# Heat_Controller.net
KiCad netlist of a schematic drawn in Altium Designer
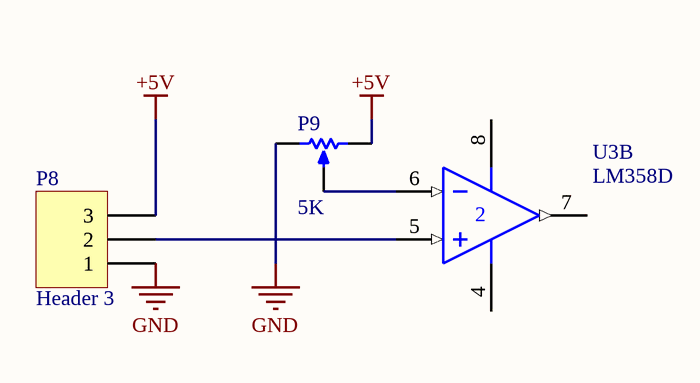
[diagram p0: Heat Controller.SchDoc]

(export (version "E")
  (design (tool "Eeschema 10.0.6"))
  (components
    (comp (ref "P8")
      (value "Header 3")
      (footprint "HDR1X3")
      (description "Header, 3-Pin")
      (fields (field (name "PUBLISHER") "Altium Limited"))
      (libsource (lib "Miscellaneous Connectors") (part "Header 3"))
    )
    (comp (ref "P9")
      (value "5K")
      (footprint "TRIMPOT-3296W")
      (libsource (lib "CustomLibrary") (part "TRIMPOT"))
    )
    (comp (ref "U3")
      (value "LM358D")
      (footprint "751-02_N")
      (description "Dual Low-Power Operational Amplifier")
      (fields (field (name "PUBLISHER") "Altium Limited"))
      (libsource (lib "Motorola Amplifier Operational Amplifier") (part "LM358D"))
    )
  )
  (nets
    (net (code "1") (name "+5V") (class "Default")
      (node (ref "P8") (pin "3") (pinfunction "3_3") (pintype "passive"))
      (node (ref "P9") (pin "3") (pinfunction "BOT_3") (pintype "passive"))
    )
    (net (code "2") (name "GND") (class "Default")
      (node (ref "P8") (pin "1") (pinfunction "1_1") (pintype "passive"))
      (node (ref "P9") (pin "1") (pinfunction "TOP_1") (pintype "passive"))
    )
    (net (code "3") (name "Net-(P9-TAP)") (class "Default")
      (node (ref "P9") (pin "2") (pinfunction "TAP_2") (pintype "passive"))
      (node (ref "U3") (pin "6") (pinfunction "IN-_6") (pintype "input"))
    )
    (net (code "4") (name "Net-(U3B-IN+)") (class "Default")
      (node (ref "P8") (pin "2") (pinfunction "2_2") (pintype "passive"))
      (node (ref "U3") (pin "5") (pinfunction "IN+_5") (pintype "input"))
    )
    (net (code "5") (name "unconnected-(U3B-OUT-Pad7)") (class "Default")
      (node (ref "U3") (pin "7") (pinfunction "OUT_7") (pintype "output"))
    )
    (net (code "6") (name "unconnected-(U3B-V+-Pad8)") (class "Default")
      (node (ref "U3") (pin "8") (pinfunction "V+_8") (pintype "power_in"))
    )
    (net (code "7") (name "unconnected-(U3B-V--Pad4)") (class "Default")
      (node (ref "U3") (pin "4") (pinfunction "V-_4") (pintype "power_in"))
    )
  )
)
